# Bike_sharing_system_final_one_with_30_pi.net
KiCad netlist of a schematic drawn in EasyEDA
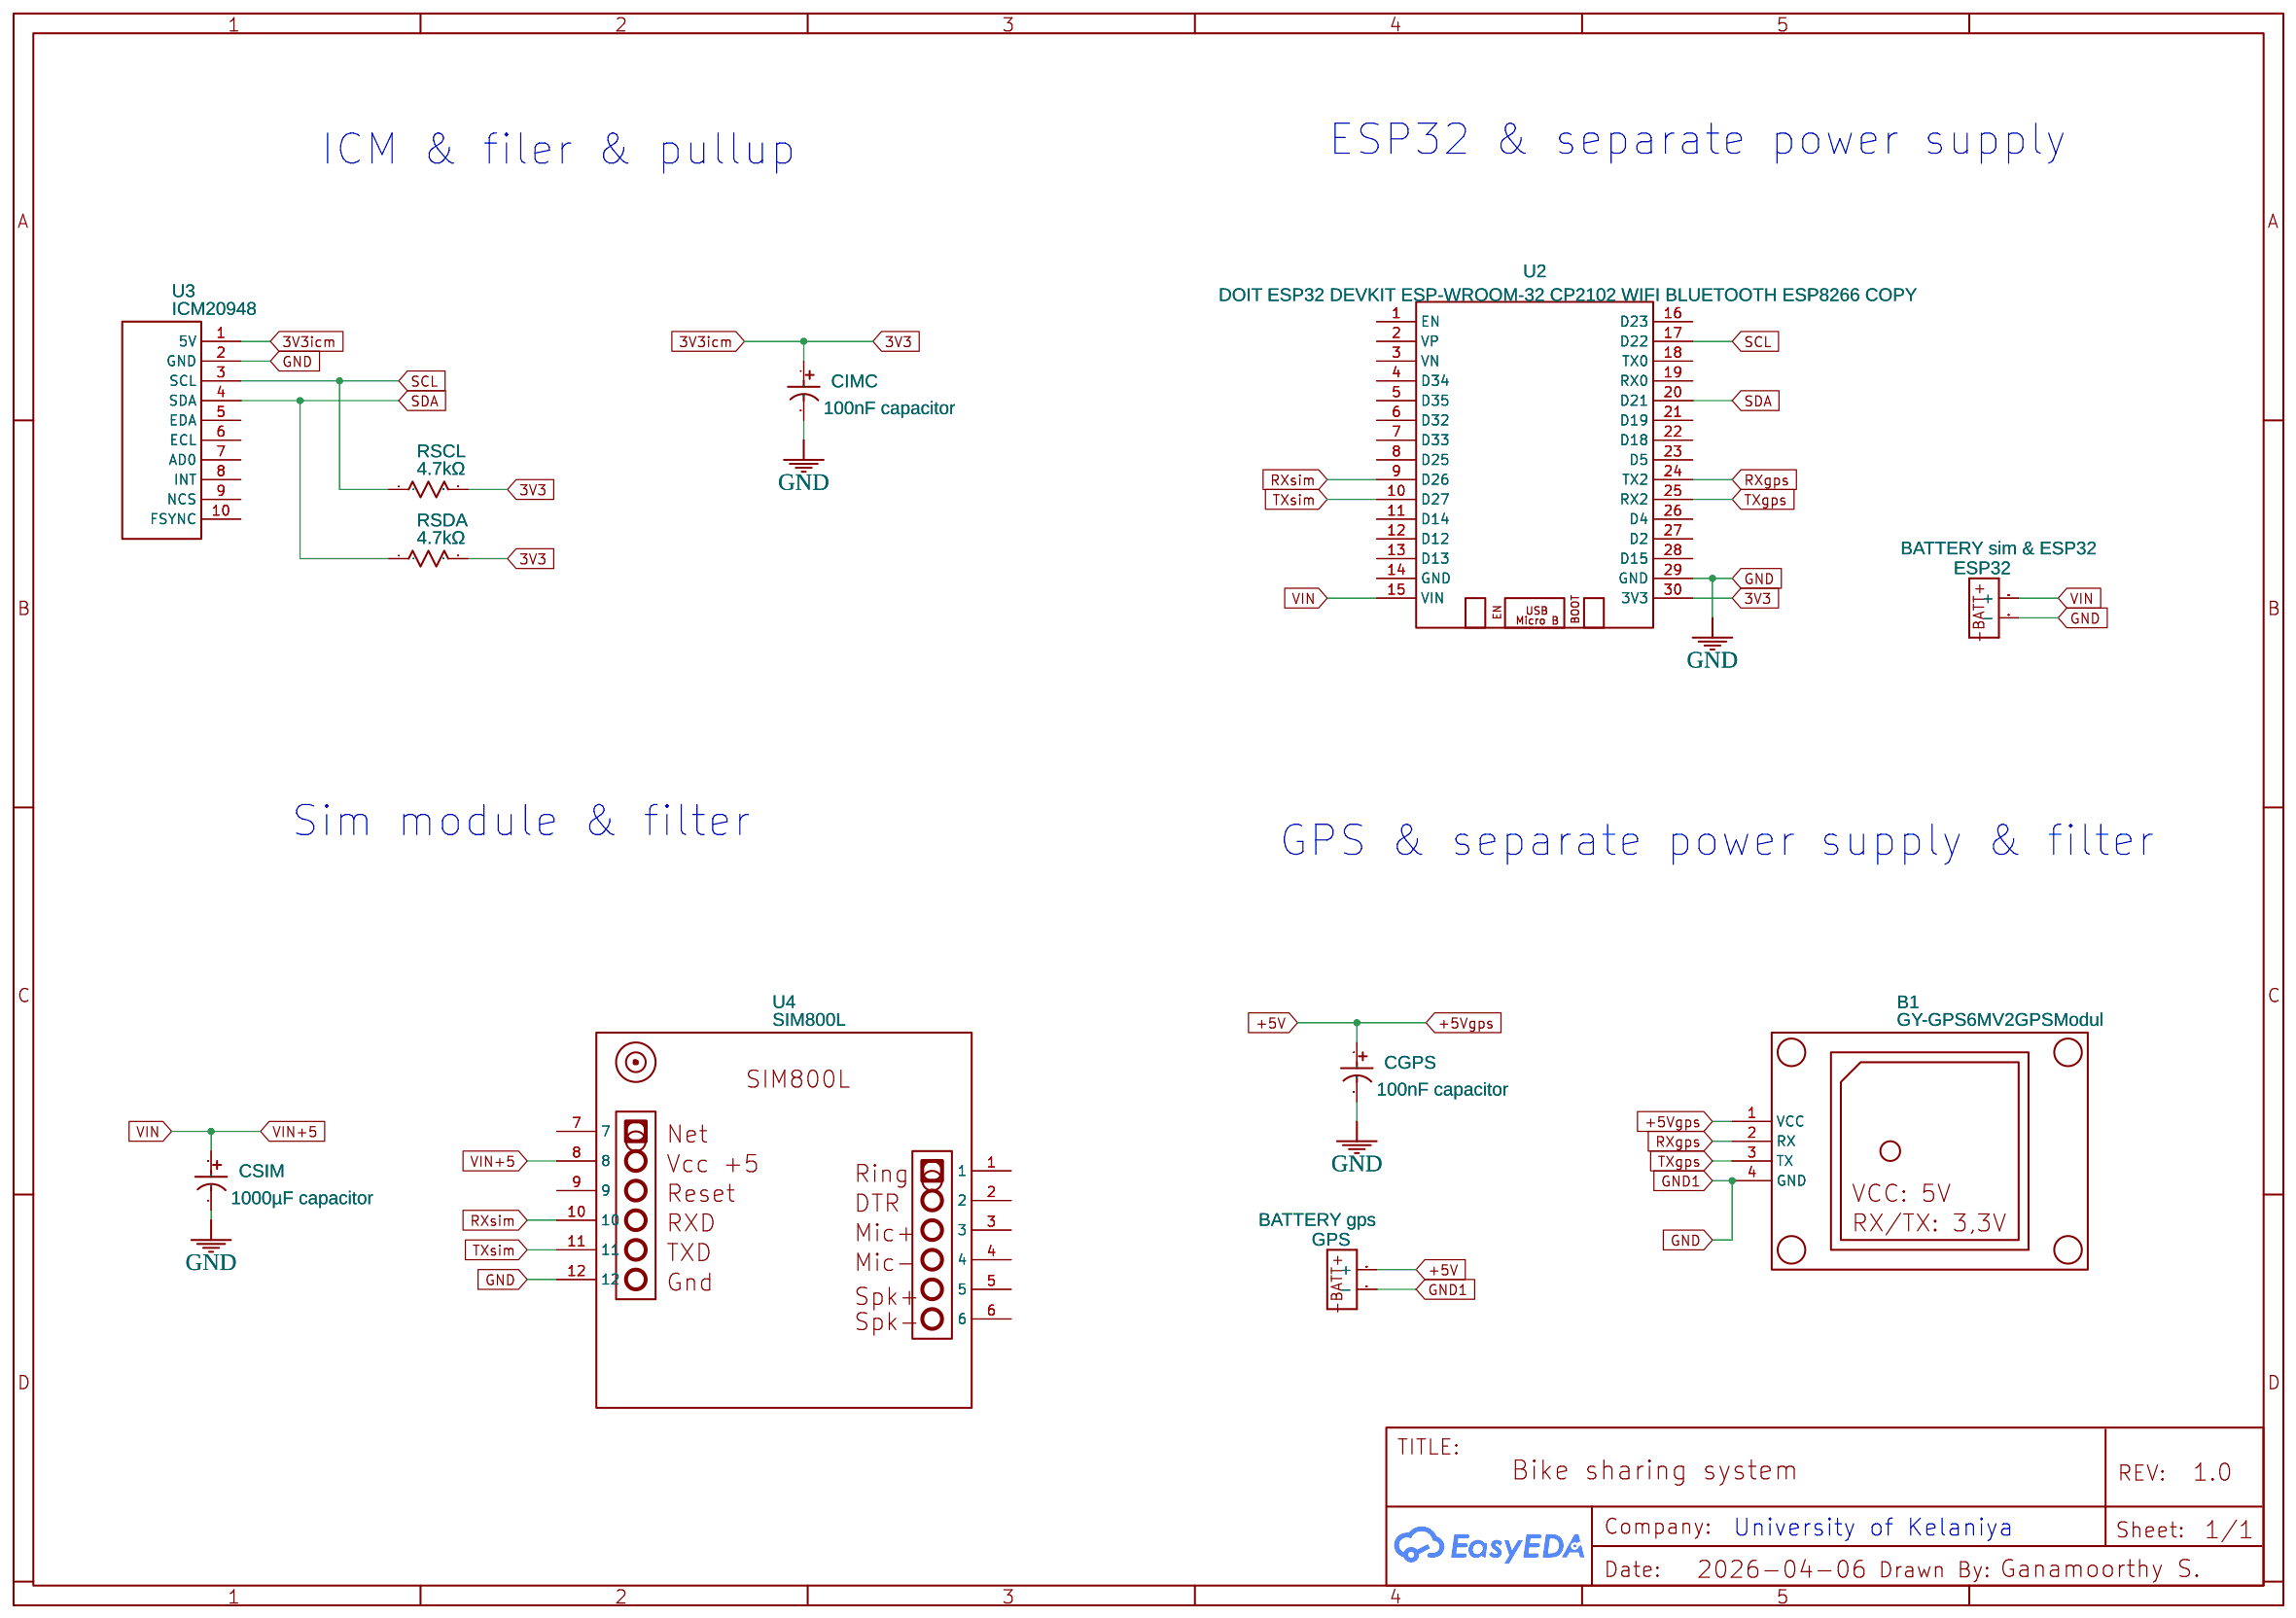
[diagram p0: schematic sheet]

(export (version "E")
  (design (tool "Eeschema 10.0.6"))
  (components
    (comp (ref "B1") (value "GY-GPS6MV2GPSModul") (libsource (lib "") (part "GY-GPS6MV2GPSModul")))
    (comp (ref "CGPS")
      (value "100nF capacitor")
      (fields
        (field (name "Manufacturer Part") "KM476M016D11RR0VH2FP0")
        (field (name "Manufacturer") "CX(承兴)")
      )
      (libsource (lib "") (part "CAPACITOR 680UF COPY_1"))
    )
    (comp (ref "CIMC")
      (value "100nF capacitor")
      (fields
        (field (name "Manufacturer Part") "KM476M016D11RR0VH2FP0")
        (field (name "Manufacturer") "CX(承兴)")
      )
      (libsource (lib "") (part "CAPACITOR 680UF COPY_2"))
    )
    (comp (ref "CSIM")
      (value "1000µF capacitor")
      (fields
        (field (name "Manufacturer Part") "KM476M016D11RR0VH2FP0")
        (field (name "Manufacturer") "CX(承兴)")
      )
      (libsource (lib "") (part "CAPACITOR 680UF COPY"))
    )
    (comp (ref "ESP32") (value "BATTERY sim & ESP32") (libsource (lib "") (part "2 PIN CON (BATTERY)")))
    (comp (ref "GPS") (value "BATTERY gps") (libsource (lib "") (part "2 PIN CON (BATTERY)_1")))
    (comp (ref "RSCL")
      (value "4.7kΩ")
      (fields (field (name "Manufacturer Part") "Resister"))
      (libsource (lib "") (part "RESISTER COPY"))
    )
    (comp (ref "RSDA")
      (value "4.7kΩ")
      (fields (field (name "Manufacturer Part") "Resister"))
      (libsource (lib "") (part "RESISTER COPY_1"))
    )
    (comp (ref "U2")
      (value "DOIT ESP32 DEVKIT ESP-WROOM-32 CP2102 WIFI BLUETOOTH ESP8266 COPY")
      (libsource (lib "") (part "DOIT ESP32 DEVKIT ESP-WROOM-32 CP2102 WIFI BLUETOOTH ESP8266 COPY"))
    )
    (comp (ref "U3") (value "ICM20948") (libsource (lib "") (part "ICM20948")))
    (comp (ref "U4") (value "SIM800L") (libsource (lib "") (part "SIM800L")))
  )
  (nets
    (net (code "1") (name "+5V") (class "Default")
      (node (ref "B1") (pin "1") (pinfunction "VCC_1") (pintype "unspecified"))
      (node (ref "CGPS") (pin "1") (pinfunction "1_1") (pintype "unspecified"))
      (node (ref "GPS") (pin "BAT+") (pinfunction "+_BAT+") (pintype "unspecified"))
    )
    (net (code "2") (name "3V3") (class "Default")
      (node (ref "CIMC") (pin "1") (pinfunction "1_1") (pintype "unspecified"))
      (node (ref "RSCL") (pin "2") (pinfunction "2_2") (pintype "unspecified"))
      (node (ref "RSDA") (pin "2") (pinfunction "2_2") (pintype "unspecified"))
      (node (ref "U2") (pin "30") (pinfunction "3V3_30") (pintype "bidirectional"))
      (node (ref "U3") (pin "1") (pinfunction "5V_1") (pintype "unspecified"))
    )
    (net (code "3") (name "GND") (class "Default")
      (node (ref "B1") (pin "4") (pinfunction "GND_4") (pintype "unspecified"))
      (node (ref "CGPS") (pin "2") (pinfunction "2_2") (pintype "unspecified"))
      (node (ref "CIMC") (pin "2") (pinfunction "2_2") (pintype "unspecified"))
      (node (ref "CSIM") (pin "2") (pinfunction "2_2") (pintype "unspecified"))
      (node (ref "ESP32") (pin "BAT-") (pinfunction "-_BAT-") (pintype "unspecified"))
      (node (ref "GPS") (pin "BAT-") (pinfunction "-_BAT-") (pintype "unspecified"))
      (node (ref "U2") (pin "29") (pinfunction "GND_29") (pintype "bidirectional"))
      (node (ref "U3") (pin "2") (pinfunction "GND_2") (pintype "unspecified"))
      (node (ref "U4") (pin "12") (pinfunction "12_12") (pintype "unspecified"))
    )
    (net (code "4") (name "RXgps") (class "Default")
      (node (ref "B1") (pin "2") (pinfunction "RX_2") (pintype "unspecified"))
      (node (ref "U2") (pin "24") (pinfunction "TX2_24") (pintype "bidirectional"))
    )
    (net (code "5") (name "RXsim") (class "Default")
      (node (ref "U2") (pin "9") (pinfunction "D26_9") (pintype "bidirectional"))
      (node (ref "U4") (pin "10") (pinfunction "10_10") (pintype "unspecified"))
    )
    (net (code "6") (name "SCL") (class "Default")
      (node (ref "RSCL") (pin "1") (pinfunction "1_1") (pintype "unspecified"))
      (node (ref "U2") (pin "17") (pinfunction "D22_17") (pintype "bidirectional"))
      (node (ref "U3") (pin "3") (pinfunction "SCL_3") (pintype "unspecified"))
    )
    (net (code "7") (name "SDA") (class "Default")
      (node (ref "RSDA") (pin "1") (pinfunction "1_1") (pintype "unspecified"))
      (node (ref "U2") (pin "20") (pinfunction "D21_20") (pintype "bidirectional"))
      (node (ref "U3") (pin "4") (pinfunction "SDA_4") (pintype "unspecified"))
    )
    (net (code "8") (name "TXgps") (class "Default")
      (node (ref "B1") (pin "3") (pinfunction "TX_3") (pintype "unspecified"))
      (node (ref "U2") (pin "25") (pinfunction "RX2_25") (pintype "bidirectional"))
    )
    (net (code "9") (name "TXsim") (class "Default")
      (node (ref "U2") (pin "10") (pinfunction "D27_10") (pintype "bidirectional"))
      (node (ref "U4") (pin "11") (pinfunction "11_11") (pintype "unspecified"))
    )
    (net (code "10") (name "VIN") (class "Default")
      (node (ref "CSIM") (pin "1") (pinfunction "1_1") (pintype "unspecified"))
      (node (ref "ESP32") (pin "BAT+") (pinfunction "+_BAT+") (pintype "unspecified"))
      (node (ref "U2") (pin "15") (pinfunction "VIN_15") (pintype "input"))
      (node (ref "U4") (pin "8") (pinfunction "8_8") (pintype "unspecified"))
    )
    (net (code "11") (name "unconnected-(U2-D2-Pad27)") (class "Default")
      (node (ref "U2") (pin "27") (pinfunction "D2_27") (pintype "bidirectional"))
    )
    (net (code "12") (name "unconnected-(U2-D4-Pad26)") (class "Default")
      (node (ref "U2") (pin "26") (pinfunction "D4_26") (pintype "bidirectional"))
    )
    (net (code "13") (name "unconnected-(U2-D5-Pad23)") (class "Default")
      (node (ref "U2") (pin "23") (pinfunction "D5_23") (pintype "bidirectional"))
    )
    (net (code "14") (name "unconnected-(U2-D12-Pad12)") (class "Default")
      (node (ref "U2") (pin "12") (pinfunction "D12_12") (pintype "bidirectional"))
    )
    (net (code "15") (name "unconnected-(U2-D13-Pad13)") (class "Default")
      (node (ref "U2") (pin "13") (pinfunction "D13_13") (pintype "bidirectional"))
    )
    (net (code "16") (name "unconnected-(U2-D14-Pad11)") (class "Default")
      (node (ref "U2") (pin "11") (pinfunction "D14_11") (pintype "bidirectional"))
    )
    (net (code "17") (name "unconnected-(U2-D15-Pad28)") (class "Default")
      (node (ref "U2") (pin "28") (pinfunction "D15_28") (pintype "bidirectional"))
    )
    (net (code "18") (name "unconnected-(U2-D18-Pad22)") (class "Default")
      (node (ref "U2") (pin "22") (pinfunction "D18_22") (pintype "bidirectional"))
    )
    (net (code "19") (name "unconnected-(U2-D19-Pad21)") (class "Default")
      (node (ref "U2") (pin "21") (pinfunction "D19_21") (pintype "bidirectional"))
    )
    (net (code "20") (name "unconnected-(U2-D23-Pad16)") (class "Default")
      (node (ref "U2") (pin "16") (pinfunction "D23_16") (pintype "bidirectional"))
    )
    (net (code "21") (name "unconnected-(U2-D25-Pad8)") (class "Default")
      (node (ref "U2") (pin "8") (pinfunction "D25_8") (pintype "bidirectional"))
    )
    (net (code "22") (name "unconnected-(U2-D32-Pad6)") (class "Default")
      (node (ref "U2") (pin "6") (pinfunction "D32_6") (pintype "bidirectional"))
    )
    (net (code "23") (name "unconnected-(U2-D33-Pad7)") (class "Default")
      (node (ref "U2") (pin "7") (pinfunction "D33_7") (pintype "bidirectional"))
    )
    (net (code "24") (name "unconnected-(U2-D34-Pad4)") (class "Default")
      (node (ref "U2") (pin "4") (pinfunction "D34_4") (pintype "input"))
    )
    (net (code "25") (name "unconnected-(U2-D35-Pad5)") (class "Default")
      (node (ref "U2") (pin "5") (pinfunction "D35_5") (pintype "input"))
    )
    (net (code "26") (name "unconnected-(U2-EN-Pad1)") (class "Default")
      (node (ref "U2") (pin "1") (pinfunction "EN_1") (pintype "bidirectional"))
    )
    (net (code "27") (name "unconnected-(U2-GND-Pad14)") (class "Default")
      (node (ref "U2") (pin "14") (pinfunction "GND_14") (pintype "bidirectional"))
    )
    (net (code "28") (name "unconnected-(U2-RX0-Pad19)") (class "Default")
      (node (ref "U2") (pin "19") (pinfunction "RX0_19") (pintype "bidirectional"))
    )
    (net (code "29") (name "unconnected-(U2-TX0-Pad18)") (class "Default")
      (node (ref "U2") (pin "18") (pinfunction "TX0_18") (pintype "bidirectional"))
    )
    (net (code "30") (name "unconnected-(U2-VN-Pad3)") (class "Default")
      (node (ref "U2") (pin "3") (pinfunction "VN_3") (pintype "input"))
    )
    (net (code "31") (name "unconnected-(U2-VP-Pad2)") (class "Default")
      (node (ref "U2") (pin "2") (pinfunction "VP_2") (pintype "input"))
    )
    (net (code "32") (name "unconnected-(U3-AD0-Pad7)") (class "Default")
      (node (ref "U3") (pin "7") (pinfunction "AD0_7") (pintype "unspecified"))
    )
    (net (code "33") (name "unconnected-(U3-ECL-Pad6)") (class "Default")
      (node (ref "U3") (pin "6") (pinfunction "ECL_6") (pintype "unspecified"))
    )
    (net (code "34") (name "unconnected-(U3-EDA-Pad5)") (class "Default")
      (node (ref "U3") (pin "5") (pinfunction "EDA_5") (pintype "unspecified"))
    )
    (net (code "35") (name "unconnected-(U3-FSYNC-Pad10)") (class "Default")
      (node (ref "U3") (pin "10") (pinfunction "FSYNC_10") (pintype "unspecified"))
    )
    (net (code "36") (name "unconnected-(U3-INT-Pad8)") (class "Default")
      (node (ref "U3") (pin "8") (pinfunction "INT_8") (pintype "unspecified"))
    )
    (net (code "37") (name "unconnected-(U3-NCS-Pad9)") (class "Default")
      (node (ref "U3") (pin "9") (pinfunction "NCS_9") (pintype "unspecified"))
    )
    (net (code "38") (name "unconnected-(U4-Pad1)") (class "Default")
      (node (ref "U4") (pin "1") (pinfunction "1_1") (pintype "unspecified"))
    )
    (net (code "39") (name "unconnected-(U4-Pad2)") (class "Default")
      (node (ref "U4") (pin "2") (pinfunction "2_2") (pintype "unspecified"))
    )
    (net (code "40") (name "unconnected-(U4-Pad3)") (class "Default")
      (node (ref "U4") (pin "3") (pinfunction "3_3") (pintype "unspecified"))
    )
    (net (code "41") (name "unconnected-(U4-Pad4)") (class "Default")
      (node (ref "U4") (pin "4") (pinfunction "4_4") (pintype "unspecified"))
    )
    (net (code "42") (name "unconnected-(U4-Pad5)") (class "Default")
      (node (ref "U4") (pin "5") (pinfunction "5_5") (pintype "unspecified"))
    )
    (net (code "43") (name "unconnected-(U4-Pad6)") (class "Default")
      (node (ref "U4") (pin "6") (pinfunction "6_6") (pintype "unspecified"))
    )
    (net (code "44") (name "unconnected-(U4-Pad7)") (class "Default")
      (node (ref "U4") (pin "7") (pinfunction "7_7") (pintype "unspecified"))
    )
    (net (code "45") (name "unconnected-(U4-Pad9)") (class "Default")
      (node (ref "U4") (pin "9") (pinfunction "9_9") (pintype "unspecified"))
    )
  )
)
